# Engine_Room.net
KiCad netlist of a schematic drawn in EAGLE
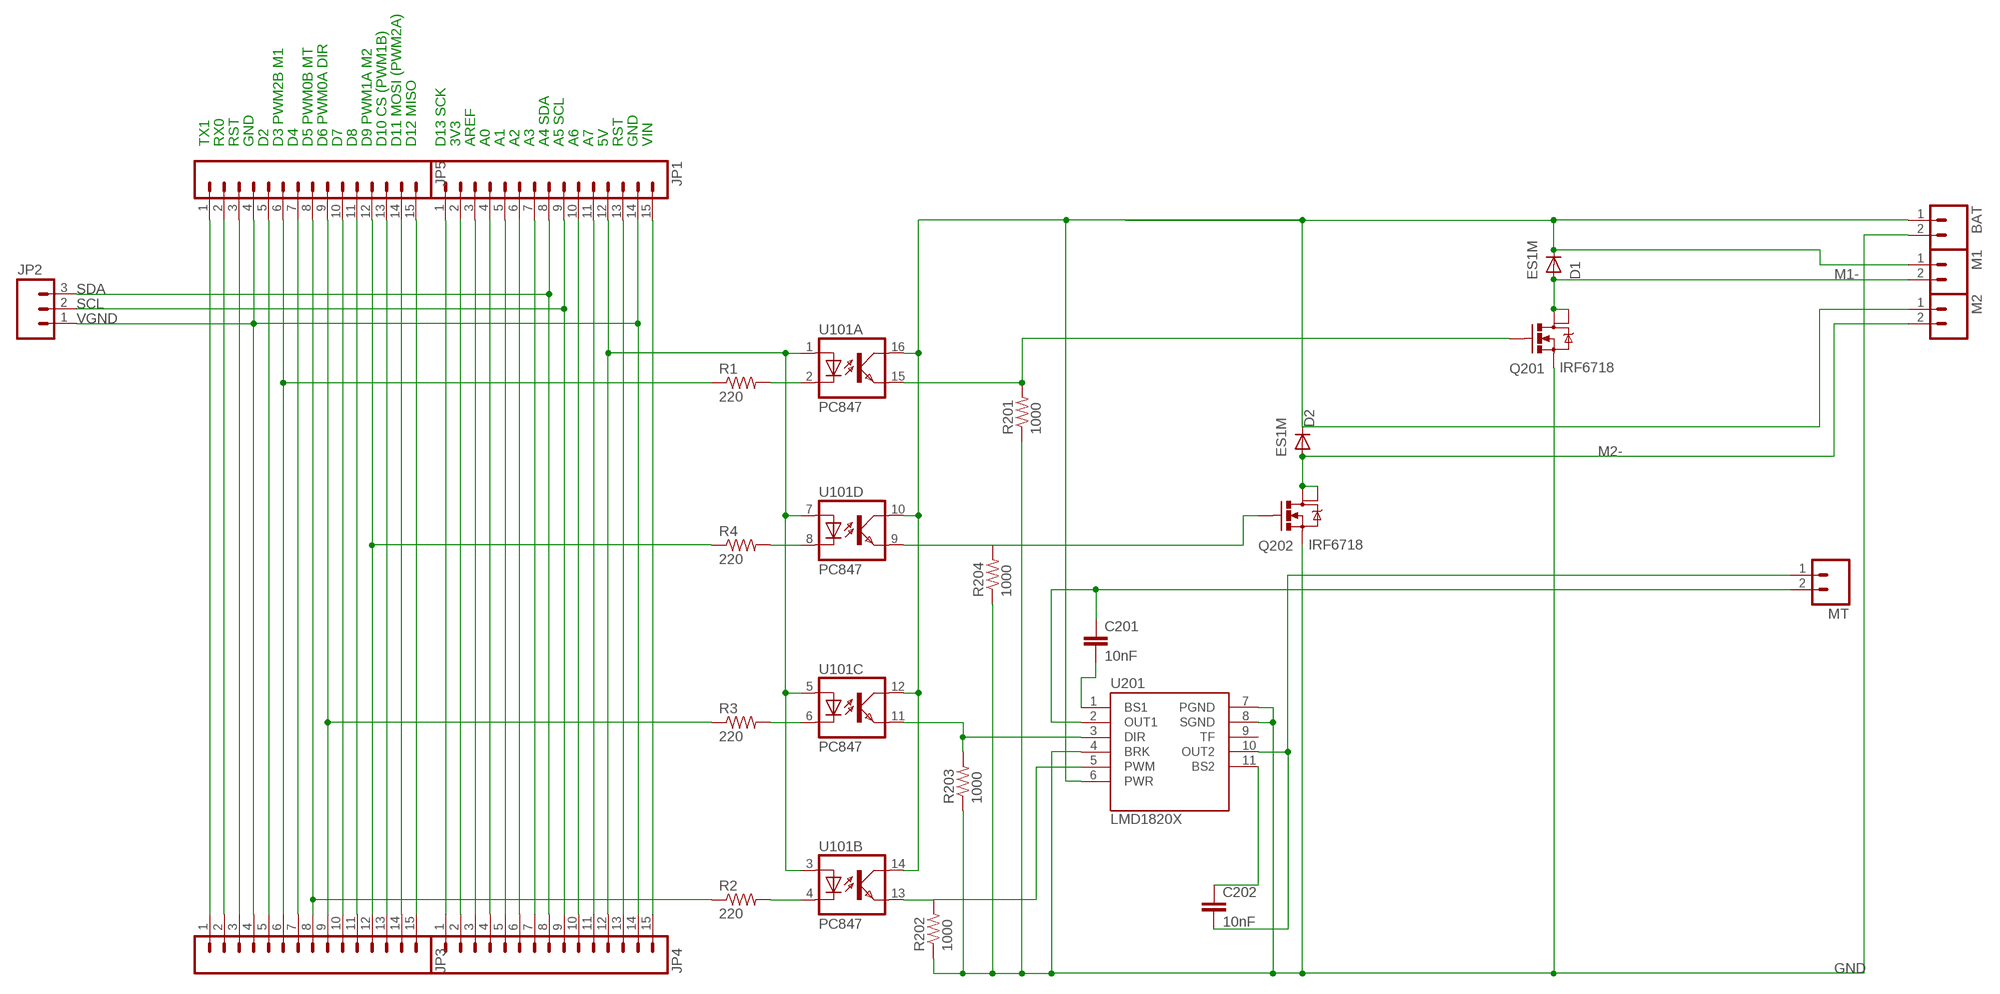
[diagram p0: schematic, sheet 1]

(export (version "E")
  (design (tool "Eeschema 10.0.6"))
  (components
    (comp (ref "BAT")
      (value "M02PTH4")
      (footprint "eagle-import:1X02_XTRA_BIG")
      (libsource (lib "eagle-import") (part "M02PTH4"))
    )
    (comp (ref "C201")
      (value "10nF")
      (footprint "eagle-import:0402-CAP")
      (libsource (lib "eagle-import") (part "CAP0402-CAP"))
    )
    (comp (ref "C202")
      (value "10nF")
      (footprint "eagle-import:0402-CAP")
      (libsource (lib "eagle-import") (part "CAP0402-CAP"))
    )
    (comp (ref "D1")
      (value "ES1M")
      (footprint "eagle-import:DO-214AC")
      (libsource (lib "eagle-import") (part "DIODE-DO-214AC"))
    )
    (comp (ref "D2")
      (value "ES1M")
      (footprint "eagle-import:DO-214AC")
      (libsource (lib "eagle-import") (part "DIODE-DO-214AC"))
    )
    (comp (ref "JP1")
      (value "M15LOCK")
      (footprint "eagle-import:1X15_LOCK")
      (libsource (lib "eagle-import") (part "M15LOCK"))
    )
    (comp (ref "JP2")
      (value "M03LOCK")
      (footprint "eagle-import:1X03_LOCK")
      (libsource (lib "eagle-import") (part "M03LOCK"))
    )
    (comp (ref "JP3")
      (value "M15")
      (footprint "eagle-import:1X15")
      (libsource (lib "eagle-import") (part "M15"))
    )
    (comp (ref "JP4")
      (value "M15")
      (footprint "eagle-import:1X15")
      (libsource (lib "eagle-import") (part "M15"))
    )
    (comp (ref "JP5")
      (value "M15LOCK")
      (footprint "eagle-import:1X15_LOCK")
      (libsource (lib "eagle-import") (part "M15LOCK"))
    )
    (comp (ref "M1")
      (value "M02PTH4")
      (footprint "eagle-import:1X02_XTRA_BIG")
      (libsource (lib "eagle-import") (part "M02PTH4"))
    )
    (comp (ref "M2")
      (value "M02PTH4")
      (footprint "eagle-import:1X02_XTRA_BIG")
      (libsource (lib "eagle-import") (part "M02PTH4"))
    )
    (comp (ref "MT")
      (value "M02PTH")
      (footprint "eagle-import:1X02")
      (libsource (lib "eagle-import") (part "M02PTH"))
    )
    (comp (ref "Q201")
      (value "IRF6718")
      (footprint "eagle-import:DIRECTFET_L6")
      (libsource (lib "eagle-import") (part "IRF6718"))
    )
    (comp (ref "Q202")
      (value "IRF6718")
      (footprint "eagle-import:DIRECTFET_L6")
      (libsource (lib "eagle-import") (part "IRF6718"))
    )
    (comp (ref "R1")
      (value "220")
      (footprint "eagle-import:0402-RES")
      (libsource (lib "eagle-import") (part "RESISTOR0402-RES"))
    )
    (comp (ref "R2")
      (value "220")
      (footprint "eagle-import:0402-RES")
      (libsource (lib "eagle-import") (part "RESISTOR0402-RES"))
    )
    (comp (ref "R3")
      (value "220")
      (footprint "eagle-import:0402-RES")
      (libsource (lib "eagle-import") (part "RESISTOR0402-RES"))
    )
    (comp (ref "R4")
      (value "220")
      (footprint "eagle-import:0402-RES")
      (libsource (lib "eagle-import") (part "RESISTOR0402-RES"))
    )
    (comp (ref "R201")
      (value "1000")
      (footprint "eagle-import:0402-RES")
      (libsource (lib "eagle-import") (part "RESISTOR0402-RES"))
    )
    (comp (ref "R202")
      (value "1000")
      (footprint "eagle-import:0402-RES")
      (libsource (lib "eagle-import") (part "RESISTOR0402-RES"))
    )
    (comp (ref "R203")
      (value "1000")
      (footprint "eagle-import:0402-RES")
      (libsource (lib "eagle-import") (part "RESISTOR0402-RES"))
    )
    (comp (ref "R204")
      (value "1000")
      (footprint "eagle-import:0402-RES")
      (libsource (lib "eagle-import") (part "RESISTOR0402-RES"))
    )
    (comp (ref "U101")
      (value "PC847")
      (footprint "eagle-import:DIL16")
      (libsource (lib "eagle-import") (part "PC847"))
    )
    (comp (ref "U201")
      (value "LMD1820X")
      (footprint "eagle-import:TO-220-11LEAD")
      (libsource (lib "eagle-import") (part "LMD1820X"))
    )
  )
  (nets
    (net (code "1") (name "/GND") (class "Default")
      (node (ref "BAT") (pin "2") (pinfunction "2_2") (pintype "passive"))
      (node (ref "Q201") (pin "S") (pinfunction "S_S") (pintype "passive"))
      (node (ref "Q202") (pin "S") (pinfunction "S_S") (pintype "passive"))
      (node (ref "R201") (pin "1") (pinfunction "1_1") (pintype "passive"))
      (node (ref "R202") (pin "1") (pinfunction "1_1") (pintype "passive"))
      (node (ref "R203") (pin "1") (pinfunction "1_1") (pintype "passive"))
      (node (ref "R204") (pin "1") (pinfunction "1_1") (pintype "passive"))
      (node (ref "U201") (pin "4") (pinfunction "BRK_4") (pintype "bidirectional"))
      (node (ref "U201") (pin "7") (pinfunction "PGND_7") (pintype "bidirectional"))
      (node (ref "U201") (pin "8") (pinfunction "SGND_8") (pintype "bidirectional"))
    )
    (net (code "2") (name "/M1-") (class "Default")
      (node (ref "D1") (pin "A") (pinfunction "A_A") (pintype "passive"))
      (node (ref "M1") (pin "2") (pinfunction "2_2") (pintype "passive"))
      (node (ref "Q201") (pin "D1") (pinfunction "D1_D1") (pintype "passive"))
      (node (ref "Q201") (pin "D2") (pinfunction "D2_D2") (pintype "passive"))
    )
    (net (code "3") (name "/M2-") (class "Default")
      (node (ref "D2") (pin "A") (pinfunction "A_A") (pintype "passive"))
      (node (ref "M2") (pin "2") (pinfunction "2_2") (pintype "passive"))
      (node (ref "Q202") (pin "D1") (pinfunction "D1_D1") (pintype "passive"))
      (node (ref "Q202") (pin "D2") (pinfunction "D2_D2") (pintype "passive"))
    )
    (net (code "4") (name "/SCL") (class "Default")
      (node (ref "JP1") (pin "9") (pinfunction "9_9") (pintype "passive"))
      (node (ref "JP2") (pin "2") (pinfunction "2_2") (pintype "passive"))
      (node (ref "JP4") (pin "9") (pinfunction "9_9") (pintype "passive"))
    )
    (net (code "5") (name "/SDA") (class "Default")
      (node (ref "JP1") (pin "8") (pinfunction "8_8") (pintype "passive"))
      (node (ref "JP2") (pin "3") (pinfunction "3_3") (pintype "passive"))
      (node (ref "JP4") (pin "8") (pinfunction "8_8") (pintype "passive"))
    )
    (net (code "6") (name "/VGND") (class "Default")
      (node (ref "JP1") (pin "14") (pinfunction "14_14") (pintype "passive"))
      (node (ref "JP2") (pin "1") (pinfunction "1_1") (pintype "passive"))
      (node (ref "JP3") (pin "4") (pinfunction "4_4") (pintype "passive"))
      (node (ref "JP4") (pin "14") (pinfunction "14_14") (pintype "passive"))
      (node (ref "JP5") (pin "4") (pinfunction "4_4") (pintype "passive"))
    )
    (net (code "7") (name "Net-(JP1-Pad1)") (class "Default")
      (node (ref "JP1") (pin "1") (pinfunction "1_1") (pintype "passive"))
      (node (ref "JP4") (pin "1") (pinfunction "1_1") (pintype "passive"))
    )
    (net (code "8") (name "Net-(JP1-Pad2)") (class "Default")
      (node (ref "JP1") (pin "2") (pinfunction "2_2") (pintype "passive"))
      (node (ref "JP4") (pin "2") (pinfunction "2_2") (pintype "passive"))
    )
    (net (code "9") (name "Net-(JP1-Pad3)") (class "Default")
      (node (ref "JP1") (pin "3") (pinfunction "3_3") (pintype "passive"))
      (node (ref "JP4") (pin "3") (pinfunction "3_3") (pintype "passive"))
    )
    (net (code "10") (name "Net-(JP1-Pad4)") (class "Default")
      (node (ref "JP1") (pin "4") (pinfunction "4_4") (pintype "passive"))
      (node (ref "JP4") (pin "4") (pinfunction "4_4") (pintype "passive"))
    )
    (net (code "11") (name "Net-(JP1-Pad5)") (class "Default")
      (node (ref "JP1") (pin "5") (pinfunction "5_5") (pintype "passive"))
      (node (ref "JP4") (pin "5") (pinfunction "5_5") (pintype "passive"))
    )
    (net (code "12") (name "Net-(JP1-Pad6)") (class "Default")
      (node (ref "JP1") (pin "6") (pinfunction "6_6") (pintype "passive"))
      (node (ref "JP4") (pin "6") (pinfunction "6_6") (pintype "passive"))
    )
    (net (code "13") (name "Net-(JP1-Pad7)") (class "Default")
      (node (ref "JP1") (pin "7") (pinfunction "7_7") (pintype "passive"))
      (node (ref "JP4") (pin "7") (pinfunction "7_7") (pintype "passive"))
    )
    (net (code "14") (name "Net-(JP1-Pad10)") (class "Default")
      (node (ref "JP1") (pin "10") (pinfunction "10_10") (pintype "passive"))
      (node (ref "JP4") (pin "10") (pinfunction "10_10") (pintype "passive"))
    )
    (net (code "15") (name "Net-(JP1-Pad11)") (class "Default")
      (node (ref "JP1") (pin "11") (pinfunction "11_11") (pintype "passive"))
      (node (ref "JP4") (pin "11") (pinfunction "11_11") (pintype "passive"))
    )
    (net (code "16") (name "Net-(JP1-Pad13)") (class "Default")
      (node (ref "JP1") (pin "13") (pinfunction "13_13") (pintype "passive"))
      (node (ref "JP4") (pin "13") (pinfunction "13_13") (pintype "passive"))
    )
    (net (code "17") (name "Net-(JP1-Pad15)") (class "Default")
      (node (ref "JP1") (pin "15") (pinfunction "15_15") (pintype "passive"))
      (node (ref "JP4") (pin "15") (pinfunction "15_15") (pintype "passive"))
    )
    (net (code "18") (name "Net-(JP3-Pad1)") (class "Default")
      (node (ref "JP3") (pin "1") (pinfunction "1_1") (pintype "passive"))
      (node (ref "JP5") (pin "1") (pinfunction "1_1") (pintype "passive"))
    )
    (net (code "19") (name "Net-(JP3-Pad2)") (class "Default")
      (node (ref "JP3") (pin "2") (pinfunction "2_2") (pintype "passive"))
      (node (ref "JP5") (pin "2") (pinfunction "2_2") (pintype "passive"))
    )
    (net (code "20") (name "Net-(JP3-Pad3)") (class "Default")
      (node (ref "JP3") (pin "3") (pinfunction "3_3") (pintype "passive"))
      (node (ref "JP5") (pin "3") (pinfunction "3_3") (pintype "passive"))
    )
    (net (code "21") (name "Net-(JP3-Pad5)") (class "Default")
      (node (ref "JP3") (pin "5") (pinfunction "5_5") (pintype "passive"))
      (node (ref "JP5") (pin "5") (pinfunction "5_5") (pintype "passive"))
    )
    (net (code "22") (name "Net-(JP3-Pad6)") (class "Default")
      (node (ref "JP3") (pin "6") (pinfunction "6_6") (pintype "passive"))
      (node (ref "JP5") (pin "6") (pinfunction "6_6") (pintype "passive"))
      (node (ref "R1") (pin "1") (pinfunction "1_1") (pintype "passive"))
    )
    (net (code "23") (name "Net-(JP3-Pad7)") (class "Default")
      (node (ref "JP3") (pin "7") (pinfunction "7_7") (pintype "passive"))
      (node (ref "JP5") (pin "7") (pinfunction "7_7") (pintype "passive"))
    )
    (net (code "24") (name "Net-(JP3-Pad8)") (class "Default")
      (node (ref "JP3") (pin "8") (pinfunction "8_8") (pintype "passive"))
      (node (ref "JP5") (pin "8") (pinfunction "8_8") (pintype "passive"))
      (node (ref "R2") (pin "1") (pinfunction "1_1") (pintype "passive"))
    )
    (net (code "25") (name "Net-(JP3-Pad9)") (class "Default")
      (node (ref "JP3") (pin "9") (pinfunction "9_9") (pintype "passive"))
      (node (ref "JP5") (pin "9") (pinfunction "9_9") (pintype "passive"))
      (node (ref "R3") (pin "1") (pinfunction "1_1") (pintype "passive"))
    )
    (net (code "26") (name "Net-(JP3-Pad10)") (class "Default")
      (node (ref "JP3") (pin "10") (pinfunction "10_10") (pintype "passive"))
      (node (ref "JP5") (pin "10") (pinfunction "10_10") (pintype "passive"))
    )
    (net (code "27") (name "Net-(JP3-Pad11)") (class "Default")
      (node (ref "JP3") (pin "11") (pinfunction "11_11") (pintype "passive"))
      (node (ref "JP5") (pin "11") (pinfunction "11_11") (pintype "passive"))
    )
    (net (code "28") (name "Net-(JP3-Pad12)") (class "Default")
      (node (ref "JP3") (pin "12") (pinfunction "12_12") (pintype "passive"))
      (node (ref "JP5") (pin "12") (pinfunction "12_12") (pintype "passive"))
      (node (ref "R4") (pin "1") (pinfunction "1_1") (pintype "passive"))
    )
    (net (code "29") (name "Net-(JP3-Pad13)") (class "Default")
      (node (ref "JP3") (pin "13") (pinfunction "13_13") (pintype "passive"))
      (node (ref "JP5") (pin "13") (pinfunction "13_13") (pintype "passive"))
    )
    (net (code "30") (name "Net-(JP3-Pad14)") (class "Default")
      (node (ref "JP3") (pin "14") (pinfunction "14_14") (pintype "passive"))
      (node (ref "JP5") (pin "14") (pinfunction "14_14") (pintype "passive"))
    )
    (net (code "31") (name "Net-(JP3-Pad15)") (class "Default")
      (node (ref "JP3") (pin "15") (pinfunction "15_15") (pintype "passive"))
      (node (ref "JP5") (pin "15") (pinfunction "15_15") (pintype "passive"))
    )
    (net (code "32") (name "Net-(U101A-A)") (class "Default")
      (node (ref "JP1") (pin "12") (pinfunction "12_12") (pintype "passive"))
      (node (ref "JP4") (pin "12") (pinfunction "12_12") (pintype "passive"))
      (node (ref "U101") (pin "1") (pinfunction "A_1") (pintype "passive"))
      (node (ref "U101") (pin "3") (pinfunction "A_3") (pintype "passive"))
      (node (ref "U101") (pin "5") (pinfunction "A_5") (pintype "passive"))
      (node (ref "U101") (pin "7") (pinfunction "A_7") (pintype "passive"))
    )
    (net (code "33") (name "Net-(U101A-C)") (class "Default")
      (node (ref "R1") (pin "2") (pinfunction "2_2") (pintype "passive"))
      (node (ref "U101") (pin "2") (pinfunction "C_2") (pintype "passive"))
    )
    (net (code "34") (name "Net-(U101A-COL)") (class "Default")
      (node (ref "BAT") (pin "1") (pinfunction "1_1") (pintype "passive"))
      (node (ref "D1") (pin "C") (pinfunction "C_C") (pintype "passive"))
      (node (ref "D2") (pin "C") (pinfunction "C_C") (pintype "passive"))
      (node (ref "M1") (pin "1") (pinfunction "1_1") (pintype "passive"))
      (node (ref "M2") (pin "1") (pinfunction "1_1") (pintype "passive"))
      (node (ref "U101") (pin "10") (pinfunction "COL_10") (pintype "passive"))
      (node (ref "U101") (pin "12") (pinfunction "COL_12") (pintype "passive"))
      (node (ref "U101") (pin "14") (pinfunction "COL_14") (pintype "passive"))
      (node (ref "U101") (pin "16") (pinfunction "COL_16") (pintype "passive"))
      (node (ref "U201") (pin "6") (pinfunction "PWR_6") (pintype "bidirectional"))
    )
    (net (code "35") (name "Net-(U101A-EMIT)") (class "Default")
      (node (ref "Q201") (pin "G") (pinfunction "G_G") (pintype "passive"))
      (node (ref "R201") (pin "2") (pinfunction "2_2") (pintype "passive"))
      (node (ref "U101") (pin "15") (pinfunction "EMIT_15") (pintype "passive"))
    )
    (net (code "36") (name "Net-(U101B-C)") (class "Default")
      (node (ref "R2") (pin "2") (pinfunction "2_2") (pintype "passive"))
      (node (ref "U101") (pin "4") (pinfunction "C_4") (pintype "passive"))
    )
    (net (code "37") (name "Net-(U101B-EMIT)") (class "Default")
      (node (ref "R202") (pin "2") (pinfunction "2_2") (pintype "passive"))
      (node (ref "U101") (pin "13") (pinfunction "EMIT_13") (pintype "passive"))
      (node (ref "U201") (pin "5") (pinfunction "PWM_5") (pintype "bidirectional"))
    )
    (net (code "38") (name "Net-(U101C-C)") (class "Default")
      (node (ref "R3") (pin "2") (pinfunction "2_2") (pintype "passive"))
      (node (ref "U101") (pin "6") (pinfunction "C_6") (pintype "passive"))
    )
    (net (code "39") (name "Net-(U101C-EMIT)") (class "Default")
      (node (ref "R203") (pin "2") (pinfunction "2_2") (pintype "passive"))
      (node (ref "U101") (pin "11") (pinfunction "EMIT_11") (pintype "passive"))
      (node (ref "U201") (pin "3") (pinfunction "DIR_3") (pintype "bidirectional"))
    )
    (net (code "40") (name "Net-(U101D-C)") (class "Default")
      (node (ref "R4") (pin "2") (pinfunction "2_2") (pintype "passive"))
      (node (ref "U101") (pin "8") (pinfunction "C_8") (pintype "passive"))
    )
    (net (code "41") (name "Net-(U101D-EMIT)") (class "Default")
      (node (ref "Q202") (pin "G") (pinfunction "G_G") (pintype "passive"))
      (node (ref "R204") (pin "2") (pinfunction "2_2") (pintype "passive"))
      (node (ref "U101") (pin "9") (pinfunction "EMIT_9") (pintype "passive"))
    )
    (net (code "42") (name "Net-(U201-BS1)") (class "Default")
      (node (ref "C201") (pin "2") (pinfunction "2_2") (pintype "passive"))
      (node (ref "U201") (pin "1") (pinfunction "BS1_1") (pintype "bidirectional"))
    )
    (net (code "43") (name "Net-(U201-BS2)") (class "Default")
      (node (ref "C202") (pin "1") (pinfunction "1_1") (pintype "passive"))
      (node (ref "U201") (pin "11") (pinfunction "BS2_11") (pintype "bidirectional"))
    )
    (net (code "44") (name "Net-(U201-OUT1)") (class "Default")
      (node (ref "C201") (pin "1") (pinfunction "1_1") (pintype "passive"))
      (node (ref "MT") (pin "2") (pinfunction "2_2") (pintype "passive"))
      (node (ref "U201") (pin "2") (pinfunction "OUT1_2") (pintype "bidirectional"))
    )
    (net (code "45") (name "Net-(U201-OUT2)") (class "Default")
      (node (ref "C202") (pin "2") (pinfunction "2_2") (pintype "passive"))
      (node (ref "MT") (pin "1") (pinfunction "1_1") (pintype "passive"))
      (node (ref "U201") (pin "10") (pinfunction "OUT2_10") (pintype "bidirectional"))
    )
    (net (code "46") (name "unconnected-(U201-TF-Pad9)") (class "Default")
      (node (ref "U201") (pin "9") (pinfunction "TF_9") (pintype "bidirectional"))
    )
  )
)
